# rgb-segment.net
KiCad netlist of a schematic drawn in EAGLE
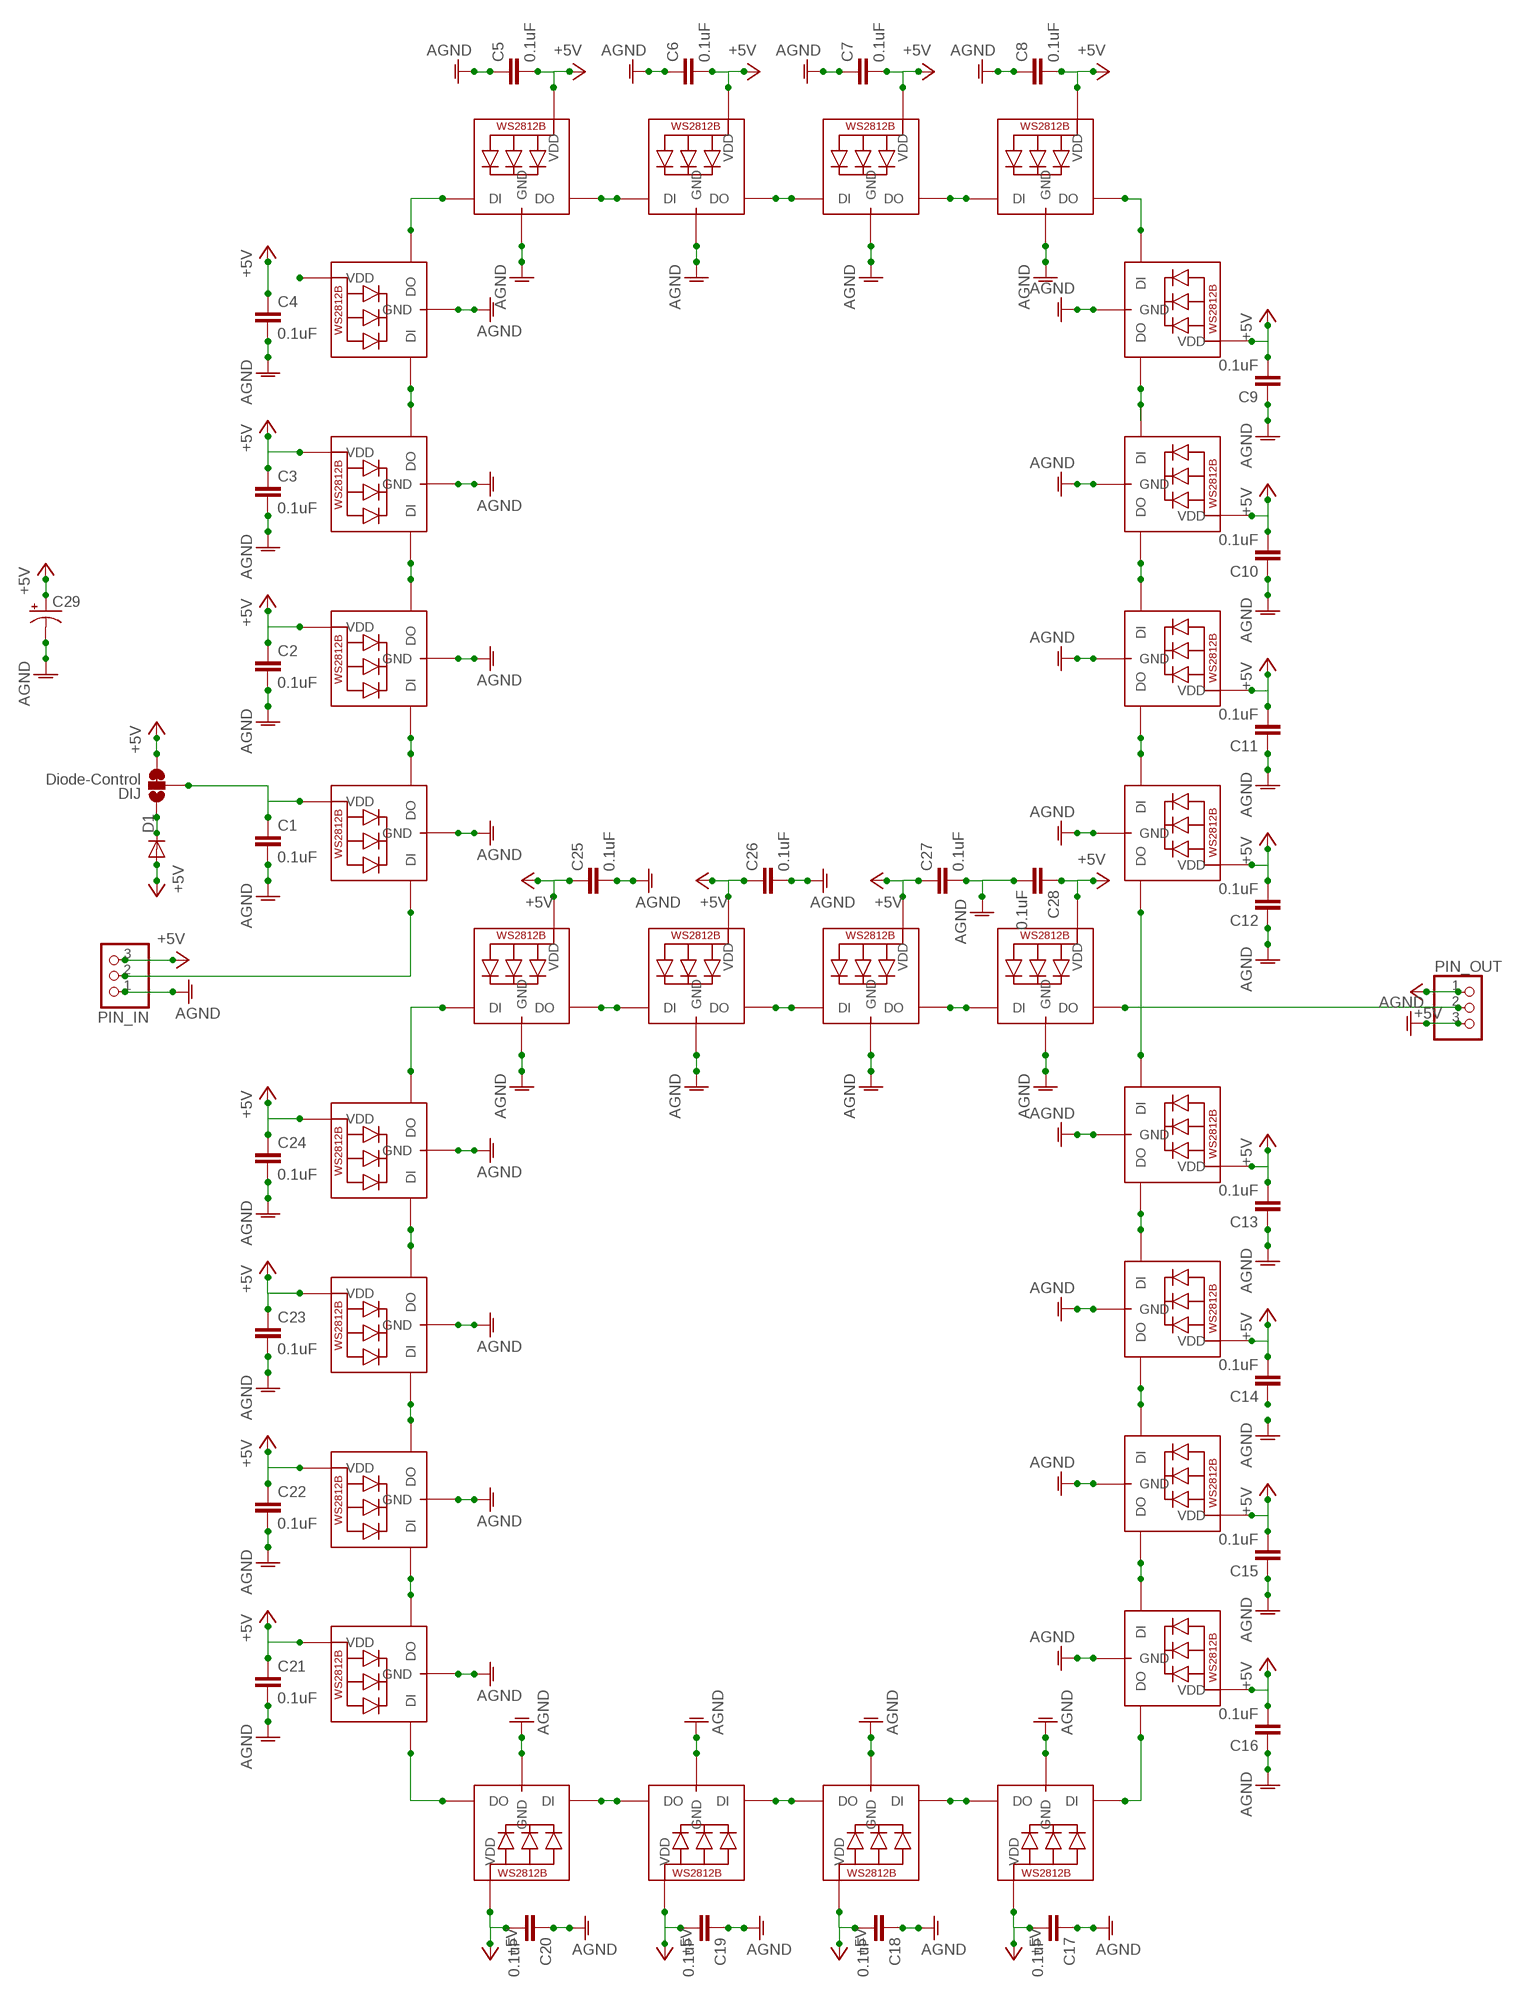
[diagram p0: schematic, sheet 1]

(export (version "E")
  (design (tool "Eeschema 10.0.6"))
  (components
    (comp (ref "C1")
      (value "0.1uF")
      (footprint "eagle-import:C0805")
      (libsource (lib "eagle-import") (part "C-EUC0805"))
    )
    (comp (ref "C2")
      (value "0.1uF")
      (footprint "eagle-import:C0805")
      (libsource (lib "eagle-import") (part "C-EUC0805"))
    )
    (comp (ref "C3")
      (value "0.1uF")
      (footprint "eagle-import:C0805")
      (libsource (lib "eagle-import") (part "C-EUC0805"))
    )
    (comp (ref "C4")
      (value "0.1uF")
      (footprint "eagle-import:C0805")
      (libsource (lib "eagle-import") (part "C-EUC0805"))
    )
    (comp (ref "C5")
      (value "0.1uF")
      (footprint "eagle-import:C0805")
      (libsource (lib "eagle-import") (part "C-EUC0805"))
    )
    (comp (ref "C6")
      (value "0.1uF")
      (footprint "eagle-import:C0805")
      (libsource (lib "eagle-import") (part "C-EUC0805"))
    )
    (comp (ref "C7")
      (value "0.1uF")
      (footprint "eagle-import:C0805")
      (libsource (lib "eagle-import") (part "C-EUC0805"))
    )
    (comp (ref "C8")
      (value "0.1uF")
      (footprint "eagle-import:C0805")
      (libsource (lib "eagle-import") (part "C-EUC0805"))
    )
    (comp (ref "C9")
      (value "0.1uF")
      (footprint "eagle-import:C0805")
      (libsource (lib "eagle-import") (part "C-EUC0805"))
    )
    (comp (ref "C10")
      (value "0.1uF")
      (footprint "eagle-import:C0805")
      (libsource (lib "eagle-import") (part "C-EUC0805"))
    )
    (comp (ref "C11")
      (value "0.1uF")
      (footprint "eagle-import:C0805")
      (libsource (lib "eagle-import") (part "C-EUC0805"))
    )
    (comp (ref "C12")
      (value "0.1uF")
      (footprint "eagle-import:C0805")
      (libsource (lib "eagle-import") (part "C-EUC0805"))
    )
    (comp (ref "C13")
      (value "0.1uF")
      (footprint "eagle-import:C0805")
      (libsource (lib "eagle-import") (part "C-EUC0805"))
    )
    (comp (ref "C14")
      (value "0.1uF")
      (footprint "eagle-import:C0805")
      (libsource (lib "eagle-import") (part "C-EUC0805"))
    )
    (comp (ref "C15")
      (value "0.1uF")
      (footprint "eagle-import:C0805")
      (libsource (lib "eagle-import") (part "C-EUC0805"))
    )
    (comp (ref "C16")
      (value "0.1uF")
      (footprint "eagle-import:C0805")
      (libsource (lib "eagle-import") (part "C-EUC0805"))
    )
    (comp (ref "C17")
      (value "0.1uF")
      (footprint "eagle-import:C0805")
      (libsource (lib "eagle-import") (part "C-EUC0805"))
    )
    (comp (ref "C18")
      (value "0.1uF")
      (footprint "eagle-import:C0805")
      (libsource (lib "eagle-import") (part "C-EUC0805"))
    )
    (comp (ref "C19")
      (value "0.1uF")
      (footprint "eagle-import:C0805")
      (libsource (lib "eagle-import") (part "C-EUC0805"))
    )
    (comp (ref "C20")
      (value "0.1uF")
      (footprint "eagle-import:C0805")
      (libsource (lib "eagle-import") (part "C-EUC0805"))
    )
    (comp (ref "C21")
      (value "0.1uF")
      (footprint "eagle-import:C0805")
      (libsource (lib "eagle-import") (part "C-EUC0805"))
    )
    (comp (ref "C22")
      (value "0.1uF")
      (footprint "eagle-import:C0805")
      (libsource (lib "eagle-import") (part "C-EUC0805"))
    )
    (comp (ref "C23")
      (value "0.1uF")
      (footprint "eagle-import:C0805")
      (libsource (lib "eagle-import") (part "C-EUC0805"))
    )
    (comp (ref "C24")
      (value "0.1uF")
      (footprint "eagle-import:C0805")
      (libsource (lib "eagle-import") (part "C-EUC0805"))
    )
    (comp (ref "C25")
      (value "0.1uF")
      (footprint "eagle-import:C0805")
      (libsource (lib "eagle-import") (part "C-EUC0805"))
    )
    (comp (ref "C26")
      (value "0.1uF")
      (footprint "eagle-import:C0805")
      (libsource (lib "eagle-import") (part "C-EUC0805"))
    )
    (comp (ref "C27")
      (value "0.1uF")
      (footprint "eagle-import:C0805")
      (libsource (lib "eagle-import") (part "C-EUC0805"))
    )
    (comp (ref "C28")
      (value "0.1uF")
      (footprint "eagle-import:C0805")
      (libsource (lib "eagle-import") (part "C-EUC0805"))
    )
    (comp (ref "C29")
      (value "CAP_POLG")
      (footprint "eagle-import:PANASONIC_G")
      (libsource (lib "eagle-import") (part "CAP_POLG"))
    )
    (comp (ref "D1")
      (value "DIODE-DO214AC")
      (footprint "eagle-import:DO214AC")
      (libsource (lib "eagle-import") (part "DIODE-DO214AC"))
    )
    (comp (ref "DIJ")
      (value "Diode-Control")
      (footprint "eagle-import:PAD-JUMPER-3-2OF3_NC_BY_TRACE_YES_SILK_FULL_BOX")
      (libsource (lib "eagle-import") (part "JUMPER-PAD-3-2OF3_NC_BY_TRACE_SMALL"))
    )
    (comp (ref "LED1")
      (value "WS2812B_5050N")
      (footprint "eagle-import:WS2812B-NARROW")
      (libsource (lib "eagle-import") (part "WS2812B_5050N"))
    )
    (comp (ref "LED2")
      (value "WS2812B_5050N")
      (footprint "eagle-import:WS2812B-NARROW")
      (libsource (lib "eagle-import") (part "WS2812B_5050N"))
    )
    (comp (ref "LED3")
      (value "WS2812B_5050N")
      (footprint "eagle-import:WS2812B-NARROW")
      (libsource (lib "eagle-import") (part "WS2812B_5050N"))
    )
    (comp (ref "LED4")
      (value "WS2812B_5050N")
      (footprint "eagle-import:WS2812B-NARROW")
      (libsource (lib "eagle-import") (part "WS2812B_5050N"))
    )
    (comp (ref "LED5")
      (value "WS2812B_5050N")
      (footprint "eagle-import:WS2812B-NARROW")
      (libsource (lib "eagle-import") (part "WS2812B_5050N"))
    )
    (comp (ref "LED6")
      (value "WS2812B_5050N")
      (footprint "eagle-import:WS2812B-NARROW")
      (libsource (lib "eagle-import") (part "WS2812B_5050N"))
    )
    (comp (ref "LED7")
      (value "WS2812B_5050N")
      (footprint "eagle-import:WS2812B-NARROW")
      (libsource (lib "eagle-import") (part "WS2812B_5050N"))
    )
    (comp (ref "LED8")
      (value "WS2812B_5050N")
      (footprint "eagle-import:WS2812B-NARROW")
      (libsource (lib "eagle-import") (part "WS2812B_5050N"))
    )
    (comp (ref "LED9")
      (value "WS2812B_5050N")
      (footprint "eagle-import:WS2812B-NARROW")
      (libsource (lib "eagle-import") (part "WS2812B_5050N"))
    )
    (comp (ref "LED10")
      (value "WS2812B_5050N")
      (footprint "eagle-import:WS2812B-NARROW")
      (libsource (lib "eagle-import") (part "WS2812B_5050N"))
    )
    (comp (ref "LED11")
      (value "WS2812B_5050N")
      (footprint "eagle-import:WS2812B-NARROW")
      (libsource (lib "eagle-import") (part "WS2812B_5050N"))
    )
    (comp (ref "LED12")
      (value "WS2812B_5050N")
      (footprint "eagle-import:WS2812B-NARROW")
      (libsource (lib "eagle-import") (part "WS2812B_5050N"))
    )
    (comp (ref "LED13")
      (value "WS2812B_5050N")
      (footprint "eagle-import:WS2812B-NARROW")
      (libsource (lib "eagle-import") (part "WS2812B_5050N"))
    )
    (comp (ref "LED14")
      (value "WS2812B_5050N")
      (footprint "eagle-import:WS2812B-NARROW")
      (libsource (lib "eagle-import") (part "WS2812B_5050N"))
    )
    (comp (ref "LED15")
      (value "WS2812B_5050N")
      (footprint "eagle-import:WS2812B-NARROW")
      (libsource (lib "eagle-import") (part "WS2812B_5050N"))
    )
    (comp (ref "LED16")
      (value "WS2812B_5050N")
      (footprint "eagle-import:WS2812B-NARROW")
      (libsource (lib "eagle-import") (part "WS2812B_5050N"))
    )
    (comp (ref "LED17")
      (value "WS2812B_5050N")
      (footprint "eagle-import:WS2812B-NARROW")
      (libsource (lib "eagle-import") (part "WS2812B_5050N"))
    )
    (comp (ref "LED18")
      (value "WS2812B_5050N")
      (footprint "eagle-import:WS2812B-NARROW")
      (libsource (lib "eagle-import") (part "WS2812B_5050N"))
    )
    (comp (ref "LED19")
      (value "WS2812B_5050N")
      (footprint "eagle-import:WS2812B-NARROW")
      (libsource (lib "eagle-import") (part "WS2812B_5050N"))
    )
    (comp (ref "LED20")
      (value "WS2812B_5050N")
      (footprint "eagle-import:WS2812B-NARROW")
      (libsource (lib "eagle-import") (part "WS2812B_5050N"))
    )
    (comp (ref "LED21")
      (value "WS2812B_5050N")
      (footprint "eagle-import:WS2812B-NARROW")
      (libsource (lib "eagle-import") (part "WS2812B_5050N"))
    )
    (comp (ref "LED22")
      (value "WS2812B_5050N")
      (footprint "eagle-import:WS2812B-NARROW")
      (libsource (lib "eagle-import") (part "WS2812B_5050N"))
    )
    (comp (ref "LED23")
      (value "WS2812B_5050N")
      (footprint "eagle-import:WS2812B-NARROW")
      (libsource (lib "eagle-import") (part "WS2812B_5050N"))
    )
    (comp (ref "LED24")
      (value "WS2812B_5050N")
      (footprint "eagle-import:WS2812B-NARROW")
      (libsource (lib "eagle-import") (part "WS2812B_5050N"))
    )
    (comp (ref "LED25")
      (value "WS2812B_5050N")
      (footprint "eagle-import:WS2812B-NARROW")
      (libsource (lib "eagle-import") (part "WS2812B_5050N"))
    )
    (comp (ref "LED26")
      (value "WS2812B_5050N")
      (footprint "eagle-import:WS2812B-NARROW")
      (libsource (lib "eagle-import") (part "WS2812B_5050N"))
    )
    (comp (ref "LED27")
      (value "WS2812B_5050N")
      (footprint "eagle-import:WS2812B-NARROW")
      (libsource (lib "eagle-import") (part "WS2812B_5050N"))
    )
    (comp (ref "LED28")
      (value "WS2812B_5050N")
      (footprint "eagle-import:WS2812B-NARROW")
      (libsource (lib "eagle-import") (part "WS2812B_5050N"))
    )
    (comp (ref "PIN_IN")
      (value "PINHD-1X3")
      (footprint "eagle-import:1X03")
      (libsource (lib "eagle-import") (part "PINHD-1X3"))
    )
    (comp (ref "PIN_OUT")
      (value "PINHD-1X3")
      (footprint "eagle-import:1X03")
      (libsource (lib "eagle-import") (part "PINHD-1X3"))
    )
  )
  (nets
    (net (code "1") (name "+5V") (class "Default")
      (node (ref "C10") (pin "2") (pinfunction "2_2") (pintype "passive"))
      (node (ref "C11") (pin "2") (pinfunction "2_2") (pintype "passive"))
      (node (ref "C12") (pin "2") (pinfunction "2_2") (pintype "passive"))
      (node (ref "C13") (pin "2") (pinfunction "2_2") (pintype "passive"))
      (node (ref "C14") (pin "2") (pinfunction "2_2") (pintype "passive"))
      (node (ref "C15") (pin "2") (pinfunction "2_2") (pintype "passive"))
      (node (ref "C16") (pin "2") (pinfunction "2_2") (pintype "passive"))
      (node (ref "C17") (pin "2") (pinfunction "2_2") (pintype "passive"))
      (node (ref "C18") (pin "2") (pinfunction "2_2") (pintype "passive"))
      (node (ref "C19") (pin "2") (pinfunction "2_2") (pintype "passive"))
      (node (ref "C2") (pin "1") (pinfunction "1_1") (pintype "passive"))
      (node (ref "C20") (pin "2") (pinfunction "2_2") (pintype "passive"))
      (node (ref "C21") (pin "1") (pinfunction "1_1") (pintype "passive"))
      (node (ref "C22") (pin "1") (pinfunction "1_1") (pintype "passive"))
      (node (ref "C23") (pin "1") (pinfunction "1_1") (pintype "passive"))
      (node (ref "C24") (pin "1") (pinfunction "1_1") (pintype "passive"))
      (node (ref "C25") (pin "1") (pinfunction "1_1") (pintype "passive"))
      (node (ref "C26") (pin "1") (pinfunction "1_1") (pintype "passive"))
      (node (ref "C27") (pin "1") (pinfunction "1_1") (pintype "passive"))
      (node (ref "C28") (pin "1") (pinfunction "1_1") (pintype "passive"))
      (node (ref "C29") (pin "+") (pinfunction "+_+") (pintype "passive"))
      (node (ref "C3") (pin "1") (pinfunction "1_1") (pintype "passive"))
      (node (ref "C4") (pin "1") (pinfunction "1_1") (pintype "passive"))
      (node (ref "C5") (pin "2") (pinfunction "2_2") (pintype "passive"))
      (node (ref "C6") (pin "2") (pinfunction "2_2") (pintype "passive"))
      (node (ref "C7") (pin "2") (pinfunction "2_2") (pintype "passive"))
      (node (ref "C8") (pin "2") (pinfunction "2_2") (pintype "passive"))
      (node (ref "C9") (pin "2") (pinfunction "2_2") (pintype "passive"))
      (node (ref "D1") (pin "A") (pinfunction "A_A") (pintype "passive"))
      (node (ref "DIJ") (pin "3") (pinfunction "3_3") (pintype "passive"))
      (node (ref "LED10") (pin "1-VDD") (pinfunction "VDD_1-VDD") (pintype "power_in"))
      (node (ref "LED11") (pin "1-VDD") (pinfunction "VDD_1-VDD") (pintype "power_in"))
      (node (ref "LED12") (pin "1-VDD") (pinfunction "VDD_1-VDD") (pintype "power_in"))
      (node (ref "LED13") (pin "1-VDD") (pinfunction "VDD_1-VDD") (pintype "power_in"))
      (node (ref "LED14") (pin "1-VDD") (pinfunction "VDD_1-VDD") (pintype "power_in"))
      (node (ref "LED15") (pin "1-VDD") (pinfunction "VDD_1-VDD") (pintype "power_in"))
      (node (ref "LED16") (pin "1-VDD") (pinfunction "VDD_1-VDD") (pintype "power_in"))
      (node (ref "LED17") (pin "1-VDD") (pinfunction "VDD_1-VDD") (pintype "power_in"))
      (node (ref "LED18") (pin "1-VDD") (pinfunction "VDD_1-VDD") (pintype "power_in"))
      (node (ref "LED19") (pin "1-VDD") (pinfunction "VDD_1-VDD") (pintype "power_in"))
      (node (ref "LED2") (pin "1-VDD") (pinfunction "VDD_1-VDD") (pintype "power_in"))
      (node (ref "LED20") (pin "1-VDD") (pinfunction "VDD_1-VDD") (pintype "power_in"))
      (node (ref "LED21") (pin "1-VDD") (pinfunction "VDD_1-VDD") (pintype "power_in"))
      (node (ref "LED22") (pin "1-VDD") (pinfunction "VDD_1-VDD") (pintype "power_in"))
      (node (ref "LED23") (pin "1-VDD") (pinfunction "VDD_1-VDD") (pintype "power_in"))
      (node (ref "LED24") (pin "1-VDD") (pinfunction "VDD_1-VDD") (pintype "power_in"))
      (node (ref "LED25") (pin "1-VDD") (pinfunction "VDD_1-VDD") (pintype "power_in"))
      (node (ref "LED26") (pin "1-VDD") (pinfunction "VDD_1-VDD") (pintype "power_in"))
      (node (ref "LED27") (pin "1-VDD") (pinfunction "VDD_1-VDD") (pintype "power_in"))
      (node (ref "LED28") (pin "1-VDD") (pinfunction "VDD_1-VDD") (pintype "power_in"))
      (node (ref "LED3") (pin "1-VDD") (pinfunction "VDD_1-VDD") (pintype "power_in"))
      (node (ref "LED5") (pin "1-VDD") (pinfunction "VDD_1-VDD") (pintype "power_in"))
      (node (ref "LED6") (pin "1-VDD") (pinfunction "VDD_1-VDD") (pintype "power_in"))
      (node (ref "LED7") (pin "1-VDD") (pinfunction "VDD_1-VDD") (pintype "power_in"))
      (node (ref "LED8") (pin "1-VDD") (pinfunction "VDD_1-VDD") (pintype "power_in"))
      (node (ref "LED9") (pin "1-VDD") (pinfunction "VDD_1-VDD") (pintype "power_in"))
      (node (ref "PIN_IN") (pin "3") (pinfunction "3_3") (pintype "passive"))
      (node (ref "PIN_OUT") (pin "1") (pinfunction "1_1") (pintype "passive"))
    )
    (net (code "2") (name "/VDD") (class "Default")
      (node (ref "LED4") (pin "1-VDD") (pinfunction "VDD_1-VDD") (pintype "power_in"))
    )
    (net (code "3") (name "AGND") (class "Default")
      (node (ref "C1") (pin "2") (pinfunction "2_2") (pintype "passive"))
      (node (ref "C10") (pin "1") (pinfunction "1_1") (pintype "passive"))
      (node (ref "C11") (pin "1") (pinfunction "1_1") (pintype "passive"))
      (node (ref "C12") (pin "1") (pinfunction "1_1") (pintype "passive"))
      (node (ref "C13") (pin "1") (pinfunction "1_1") (pintype "passive"))
      (node (ref "C15") (pin "1") (pinfunction "1_1") (pintype "passive"))
      (node (ref "C16") (pin "1") (pinfunction "1_1") (pintype "passive"))
      (node (ref "C17") (pin "1") (pinfunction "1_1") (pintype "passive"))
      (node (ref "C18") (pin "1") (pinfunction "1_1") (pintype "passive"))
      (node (ref "C19") (pin "1") (pinfunction "1_1") (pintype "passive"))
      (node (ref "C2") (pin "2") (pinfunction "2_2") (pintype "passive"))
      (node (ref "C20") (pin "1") (pinfunction "1_1") (pintype "passive"))
      (node (ref "C21") (pin "2") (pinfunction "2_2") (pintype "passive"))
      (node (ref "C22") (pin "2") (pinfunction "2_2") (pintype "passive"))
      (node (ref "C23") (pin "2") (pinfunction "2_2") (pintype "passive"))
      (node (ref "C24") (pin "2") (pinfunction "2_2") (pintype "passive"))
      (node (ref "C25") (pin "2") (pinfunction "2_2") (pintype "passive"))
      (node (ref "C26") (pin "2") (pinfunction "2_2") (pintype "passive"))
      (node (ref "C27") (pin "2") (pinfunction "2_2") (pintype "passive"))
      (node (ref "C28") (pin "2") (pinfunction "2_2") (pintype "passive"))
      (node (ref "C29") (pin "-") (pinfunction "-_-") (pintype "passive"))
      (node (ref "C3") (pin "2") (pinfunction "2_2") (pintype "passive"))
      (node (ref "C4") (pin "2") (pinfunction "2_2") (pintype "passive"))
      (node (ref "C5") (pin "1") (pinfunction "1_1") (pintype "passive"))
      (node (ref "C6") (pin "1") (pinfunction "1_1") (pintype "passive"))
      (node (ref "C7") (pin "1") (pinfunction "1_1") (pintype "passive"))
      (node (ref "C8") (pin "1") (pinfunction "1_1") (pintype "passive"))
      (node (ref "C9") (pin "1") (pinfunction "1_1") (pintype "passive"))
      (node (ref "LED1") (pin "3-GND") (pinfunction "GND_3-GND") (pintype "power_in"))
      (node (ref "LED10") (pin "3-GND") (pinfunction "GND_3-GND") (pintype "power_in"))
      (node (ref "LED11") (pin "3-GND") (pinfunction "GND_3-GND") (pintype "power_in"))
      (node (ref "LED12") (pin "3-GND") (pinfunction "GND_3-GND") (pintype "power_in"))
      (node (ref "LED13") (pin "3-GND") (pinfunction "GND_3-GND") (pintype "power_in"))
      (node (ref "LED14") (pin "3-GND") (pinfunction "GND_3-GND") (pintype "power_in"))
      (node (ref "LED15") (pin "3-GND") (pinfunction "GND_3-GND") (pintype "power_in"))
      (node (ref "LED16") (pin "3-GND") (pinfunction "GND_3-GND") (pintype "power_in"))
      (node (ref "LED17") (pin "3-GND") (pinfunction "GND_3-GND") (pintype "power_in"))
      (node (ref "LED18") (pin "3-GND") (pinfunction "GND_3-GND") (pintype "power_in"))
      (node (ref "LED19") (pin "3-GND") (pinfunction "GND_3-GND") (pintype "power_in"))
      (node (ref "LED2") (pin "3-GND") (pinfunction "GND_3-GND") (pintype "power_in"))
      (node (ref "LED20") (pin "3-GND") (pinfunction "GND_3-GND") (pintype "power_in"))
      (node (ref "LED21") (pin "3-GND") (pinfunction "GND_3-GND") (pintype "power_in"))
      (node (ref "LED22") (pin "3-GND") (pinfunction "GND_3-GND") (pintype "power_in"))
      (node (ref "LED23") (pin "3-GND") (pinfunction "GND_3-GND") (pintype "power_in"))
      (node (ref "LED24") (pin "3-GND") (pinfunction "GND_3-GND") (pintype "power_in"))
      (node (ref "LED25") (pin "3-GND") (pinfunction "GND_3-GND") (pintype "power_in"))
      (node (ref "LED26") (pin "3-GND") (pinfunction "GND_3-GND") (pintype "power_in"))
      (node (ref "LED27") (pin "3-GND") (pinfunction "GND_3-GND") (pintype "power_in"))
      (node (ref "LED28") (pin "3-GND") (pinfunction "GND_3-GND") (pintype "power_in"))
      (node (ref "LED3") (pin "3-GND") (pinfunction "GND_3-GND") (pintype "power_in"))
      (node (ref "LED4") (pin "3-GND") (pinfunction "GND_3-GND") (pintype "power_in"))
      (node (ref "LED5") (pin "3-GND") (pinfunction "GND_3-GND") (pintype "power_in"))
      (node (ref "LED6") (pin "3-GND") (pinfunction "GND_3-GND") (pintype "power_in"))
      (node (ref "LED7") (pin "3-GND") (pinfunction "GND_3-GND") (pintype "power_in"))
      (node (ref "LED8") (pin "3-GND") (pinfunction "GND_3-GND") (pintype "power_in"))
      (node (ref "LED9") (pin "3-GND") (pinfunction "GND_3-GND") (pintype "power_in"))
      (node (ref "PIN_IN") (pin "1") (pinfunction "1_1") (pintype "passive"))
      (node (ref "PIN_OUT") (pin "3") (pinfunction "3_3") (pintype "passive"))
    )
    (net (code "4") (name "Net-(D1-PadC)") (class "Default")
      (node (ref "D1") (pin "C") (pinfunction "C_C") (pintype "passive"))
      (node (ref "DIJ") (pin "1") (pinfunction "1_1") (pintype "passive"))
    )
    (net (code "5") (name "Net-(LED1-DI)") (class "Default")
      (node (ref "LED1") (pin "4-DIN") (pinfunction "DI_4-DIN") (pintype "input"))
      (node (ref "PIN_IN") (pin "2") (pinfunction "2_2") (pintype "passive"))
    )
    (net (code "6") (name "Net-(LED1-DO)") (class "Default")
      (node (ref "LED1") (pin "2-DOUT") (pinfunction "DO_2-DOUT") (pintype "output"))
      (node (ref "LED2") (pin "4-DIN") (pinfunction "DI_4-DIN") (pintype "input"))
    )
    (net (code "7") (name "Net-(LED1-VDD)") (class "Default")
      (node (ref "C1") (pin "1") (pinfunction "1_1") (pintype "passive"))
      (node (ref "DIJ") (pin "2") (pinfunction "2_2") (pintype "passive"))
      (node (ref "LED1") (pin "1-VDD") (pinfunction "VDD_1-VDD") (pintype "power_in"))
    )
    (net (code "8") (name "Net-(LED2-DO)") (class "Default")
      (node (ref "LED2") (pin "2-DOUT") (pinfunction "DO_2-DOUT") (pintype "output"))
      (node (ref "LED3") (pin "4-DIN") (pinfunction "DI_4-DIN") (pintype "input"))
    )
    (net (code "9") (name "Net-(LED3-DO)") (class "Default")
      (node (ref "LED3") (pin "2-DOUT") (pinfunction "DO_2-DOUT") (pintype "output"))
      (node (ref "LED4") (pin "4-DIN") (pinfunction "DI_4-DIN") (pintype "input"))
    )
    (net (code "10") (name "Net-(LED4-DO)") (class "Default")
      (node (ref "LED4") (pin "2-DOUT") (pinfunction "DO_2-DOUT") (pintype "output"))
      (node (ref "LED5") (pin "4-DIN") (pinfunction "DI_4-DIN") (pintype "input"))
    )
    (net (code "11") (name "Net-(LED5-DO)") (class "Default")
      (node (ref "LED5") (pin "2-DOUT") (pinfunction "DO_2-DOUT") (pintype "output"))
      (node (ref "LED6") (pin "4-DIN") (pinfunction "DI_4-DIN") (pintype "input"))
    )
    (net (code "12") (name "Net-(LED6-DO)") (class "Default")
      (node (ref "LED6") (pin "2-DOUT") (pinfunction "DO_2-DOUT") (pintype "output"))
      (node (ref "LED7") (pin "4-DIN") (pinfunction "DI_4-DIN") (pintype "input"))
    )
    (net (code "13") (name "Net-(LED7-DO)") (class "Default")
      (node (ref "LED7") (pin "2-DOUT") (pinfunction "DO_2-DOUT") (pintype "output"))
      (node (ref "LED8") (pin "4-DIN") (pinfunction "DI_4-DIN") (pintype "input"))
    )
    (net (code "14") (name "Net-(LED8-DO)") (class "Default")
      (node (ref "LED8") (pin "2-DOUT") (pinfunction "DO_2-DOUT") (pintype "output"))
      (node (ref "LED9") (pin "4-DIN") (pinfunction "DI_4-DIN") (pintype "input"))
    )
    (net (code "15") (name "Net-(LED10-DI)") (class "Default")
      (node (ref "LED10") (pin "4-DIN") (pinfunction "DI_4-DIN") (pintype "input"))
      (node (ref "LED9") (pin "2-DOUT") (pinfunction "DO_2-DOUT") (pintype "output"))
    )
    (net (code "16") (name "Net-(LED10-DO)") (class "Default")
      (node (ref "LED10") (pin "2-DOUT") (pinfunction "DO_2-DOUT") (pintype "output"))
      (node (ref "LED11") (pin "4-DIN") (pinfunction "DI_4-DIN") (pintype "input"))
    )
    (net (code "17") (name "Net-(LED11-DO)") (class "Default")
      (node (ref "LED11") (pin "2-DOUT") (pinfunction "DO_2-DOUT") (pintype "output"))
      (node (ref "LED12") (pin "4-DIN") (pinfunction "DI_4-DIN") (pintype "input"))
    )
    (net (code "18") (name "Net-(LED12-DO)") (class "Default")
      (node (ref "LED12") (pin "2-DOUT") (pinfunction "DO_2-DOUT") (pintype "output"))
      (node (ref "LED13") (pin "4-DIN") (pinfunction "DI_4-DIN") (pintype "input"))
    )
    (net (code "19") (name "Net-(LED13-DO)") (class "Default")
      (node (ref "LED13") (pin "2-DOUT") (pinfunction "DO_2-DOUT") (pintype "output"))
      (node (ref "LED14") (pin "4-DIN") (pinfunction "DI_4-DIN") (pintype "input"))
    )
    (net (code "20") (name "Net-(LED14-DO)") (class "Default")
      (node (ref "LED14") (pin "2-DOUT") (pinfunction "DO_2-DOUT") (pintype "output"))
      (node (ref "LED15") (pin "4-DIN") (pinfunction "DI_4-DIN") (pintype "input"))
    )
    (net (code "21") (name "Net-(LED15-DO)") (class "Default")
      (node (ref "LED15") (pin "2-DOUT") (pinfunction "DO_2-DOUT") (pintype "output"))
      (node (ref "LED16") (pin "4-DIN") (pinfunction "DI_4-DIN") (pintype "input"))
    )
    (net (code "22") (name "Net-(LED16-DO)") (class "Default")
      (node (ref "LED16") (pin "2-DOUT") (pinfunction "DO_2-DOUT") (pintype "output"))
      (node (ref "LED17") (pin "4-DIN") (pinfunction "DI_4-DIN") (pintype "input"))
    )
    (net (code "23") (name "Net-(LED17-DO)") (class "Default")
      (node (ref "LED17") (pin "2-DOUT") (pinfunction "DO_2-DOUT") (pintype "output"))
      (node (ref "LED18") (pin "4-DIN") (pinfunction "DI_4-DIN") (pintype "input"))
    )
    (net (code "24") (name "Net-(LED18-DO)") (class "Default")
      (node (ref "LED18") (pin "2-DOUT") (pinfunction "DO_2-DOUT") (pintype "output"))
      (node (ref "LED19") (pin "4-DIN") (pinfunction "DI_4-DIN") (pintype "input"))
    )
    (net (code "25") (name "Net-(LED19-DO)") (class "Default")
      (node (ref "LED19") (pin "2-DOUT") (pinfunction "DO_2-DOUT") (pintype "output"))
      (node (ref "LED20") (pin "4-DIN") (pinfunction "DI_4-DIN") (pintype "input"))
    )
    (net (code "26") (name "Net-(LED20-DO)") (class "Default")
      (node (ref "LED20") (pin "2-DOUT") (pinfunction "DO_2-DOUT") (pintype "output"))
      (node (ref "LED21") (pin "4-DIN") (pinfunction "DI_4-DIN") (pintype "input"))
    )
    (net (code "27") (name "Net-(LED21-DO)") (class "Default")
      (node (ref "LED21") (pin "2-DOUT") (pinfunction "DO_2-DOUT") (pintype "output"))
      (node (ref "LED22") (pin "4-DIN") (pinfunction "DI_4-DIN") (pintype "input"))
    )
    (net (code "28") (name "Net-(LED22-DO)") (class "Default")
      (node (ref "LED22") (pin "2-DOUT") (pinfunction "DO_2-DOUT") (pintype "output"))
      (node (ref "LED23") (pin "4-DIN") (pinfunction "DI_4-DIN") (pintype "input"))
    )
    (net (code "29") (name "Net-(LED23-DO)") (class "Default")
      (node (ref "LED23") (pin "2-DOUT") (pinfunction "DO_2-DOUT") (pintype "output"))
      (node (ref "LED24") (pin "4-DIN") (pinfunction "DI_4-DIN") (pintype "input"))
    )
    (net (code "30") (name "Net-(LED24-DO)") (class "Default")
      (node (ref "LED24") (pin "2-DOUT") (pinfunction "DO_2-DOUT") (pintype "output"))
      (node (ref "LED25") (pin "4-DIN") (pinfunction "DI_4-DIN") (pintype "input"))
    )
    (net (code "31") (name "Net-(LED25-DO)") (class "Default")
      (node (ref "LED25") (pin "2-DOUT") (pinfunction "DO_2-DOUT") (pintype "output"))
      (node (ref "LED26") (pin "4-DIN") (pinfunction "DI_4-DIN") (pintype "input"))
    )
    (net (code "32") (name "Net-(LED26-DO)") (class "Default")
      (node (ref "LED26") (pin "2-DOUT") (pinfunction "DO_2-DOUT") (pintype "output"))
      (node (ref "LED27") (pin "4-DIN") (pinfunction "DI_4-DIN") (pintype "input"))
    )
    (net (code "33") (name "Net-(LED27-DO)") (class "Default")
      (node (ref "LED27") (pin "2-DOUT") (pinfunction "DO_2-DOUT") (pintype "output"))
      (node (ref "LED28") (pin "4-DIN") (pinfunction "DI_4-DIN") (pintype "input"))
    )
    (net (code "34") (name "Net-(LED28-DO)") (class "Default")
      (node (ref "LED28") (pin "2-DOUT") (pinfunction "DO_2-DOUT") (pintype "output"))
      (node (ref "PIN_OUT") (pin "2") (pinfunction "2_2") (pintype "passive"))
    )
    (net (code "35") (name "unconnected-(C14-Pad1)") (class "Default")
      (node (ref "C14") (pin "1") (pinfunction "1_1") (pintype "passive"))
    )
  )
)
